# 01-UART.net
KiCad netlist of a schematic drawn in Altium Designer
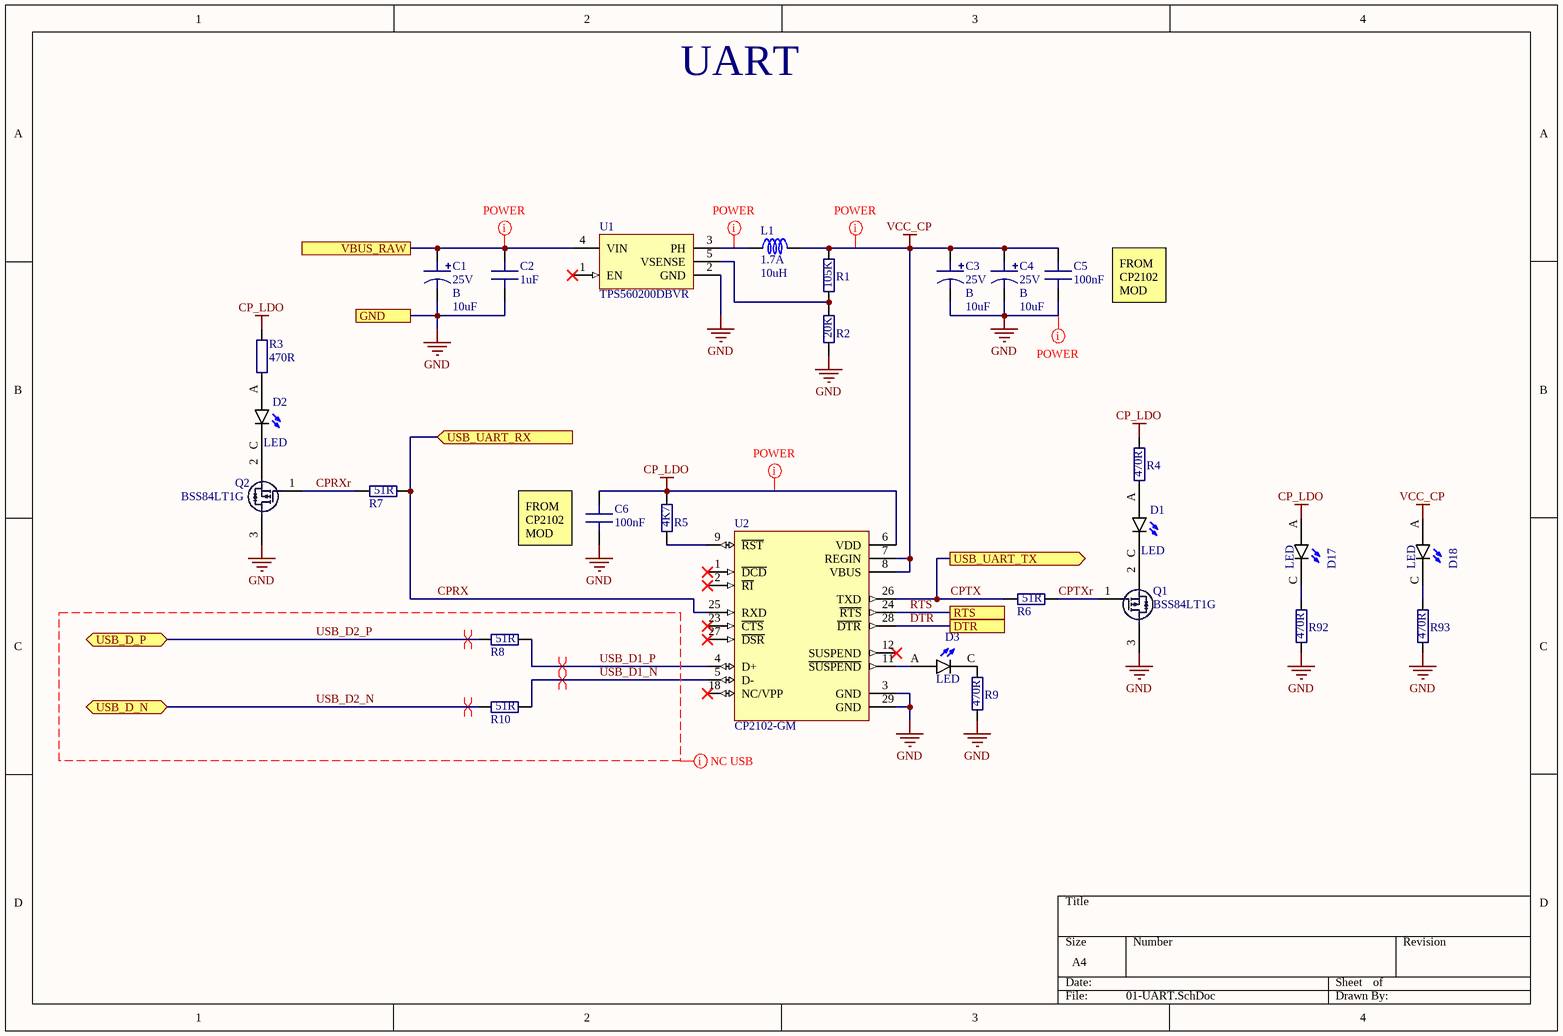
[diagram p0: 01-UART.SchDoc]

(export (version "E")
  (design (tool "Eeschema 10.0.6"))
  (components
    (comp (ref "C1")
      (value "10uF")
      (footprint "CAP_SIZE_B")
      (description "Tantalum capacitor")
      (fields (field (name "VOLTAGE") "25V") (field (name "SIZE") "B"))
      (libsource (lib "A.Shelestov_Capacitors") (part "CAP_B_10uF_25V"))
    )
    (comp (ref "C2")
      (value "1uF")
      (footprint "C0805")
      (description "Ceramic capacitor")
      (fields (field (name "VOLTAGE") "25V"))
      (libsource (lib "A.Shelestov_Capacitors") (part "C0805_1uF_25V"))
    )
    (comp (ref "C3")
      (value "10uF")
      (footprint "CAP_SIZE_B")
      (description "Tantalum capacitor")
      (fields (field (name "VOLTAGE") "25V") (field (name "SIZE") "B"))
      (libsource (lib "A.Shelestov_Capacitors") (part "CAP_B_10uF_25V"))
    )
    (comp (ref "C4")
      (value "10uF")
      (footprint "CAP_SIZE_B")
      (description "Tantalum capacitor")
      (fields (field (name "VOLTAGE") "25V") (field (name "SIZE") "B"))
      (libsource (lib "A.Shelestov_Capacitors") (part "CAP_B_10uF_25V"))
    )
    (comp (ref "C5")
      (value "100nF")
      (footprint "C0603")
      (description "Ceramic capacitor")
      (fields (field (name "VOLTAGE") "16V"))
      (libsource (lib "A.Shelestov_Capacitors") (part "C0603_100nF_16V"))
    )
    (comp (ref "C6")
      (value "100nF")
      (footprint "C0603")
      (description "Ceramic capacitor")
      (fields (field (name "VOLTAGE") "16V"))
      (libsource (lib "A.Shelestov_Capacitors") (part "C0603_100nF_16V"))
    )
    (comp (ref "D1")
      (value "LED")
      (footprint "LED_0604")
      (description "Led General")
      (fields (field (name "MF") "Dialight") (field (name "MP") "598-8140-107F"))
      (libsource (lib "ComponentsLib") (part "LED"))
    )
    (comp (ref "D2")
      (value "LED")
      (footprint "LED_0604")
      (description "Led General")
      (fields (field (name "MF") "Dialight") (field (name "MP") "598-8140-107F"))
      (libsource (lib "ComponentsLib") (part "LED"))
    )
    (comp (ref "D3")
      (value "LED")
      (footprint "LED_0604")
      (description "Led General")
      (fields (field (name "MF") "Dialight") (field (name "MP") "598-8140-107F"))
      (libsource (lib "ComponentsLib") (part "LED"))
    )
    (comp (ref "D17")
      (value "LED")
      (footprint "LED_0604")
      (description "Led General")
      (fields (field (name "MF") "Dialight") (field (name "MP") "598-8140-107F"))
      (libsource (lib "ComponentsLib") (part "LED"))
    )
    (comp (ref "D18")
      (value "LED")
      (footprint "LED_0604")
      (description "Led General")
      (fields (field (name "MF") "Dialight") (field (name "MP") "598-8140-107F"))
      (libsource (lib "ComponentsLib") (part "LED"))
    )
    (comp (ref "L1")
      (value "*")
      (footprint "L_CDRH6D28")
      (description "Inductor Generic")
      (fields (field (name "CURRENT") "1.7A") (field (name "INDUCTIVITY") "10uH"))
      (libsource (lib "A.Shelestov_Inductors") (part "L_CDRH6D28_10uH_1.7A"))
    )
    (comp (ref "Q1")
      (value "BSS84LT1G")
      (footprint "SOT-23_TO-236")
      (description "Power MOSFET Single P-Channel SOT-23 -50 V, 10 ")
      (libsource (lib "ComponentsLib") (part "BSS84LT1G"))
    )
    (comp (ref "Q2")
      (value "BSS84LT1G")
      (footprint "SOT-23_TO-236")
      (description "Power MOSFET Single P-Channel SOT-23 -50 V, 10 ")
      (libsource (lib "ComponentsLib") (part "BSS84LT1G"))
    )
    (comp (ref "R1")
      (value "~")
      (footprint "R0603")
      (description "Resistor General")
      (fields (field (name "TOLERANCE") "1%") (field (name "RESISTANCE") "105K"))
      (libsource (lib "A.Shelestov_Resistors") (part "R0603_105K_1%"))
    )
    (comp (ref "R2")
      (value "~")
      (footprint "R0603")
      (description "Resistor General")
      (fields (field (name "TOLERANCE") "1%") (field (name "RESISTANCE") "20K"))
      (libsource (lib "A.Shelestov_Resistors") (part "R0603_20K_1%"))
    )
    (comp (ref "R3")
      (value "~")
      (footprint "R0603")
      (description "Resistor General")
      (fields (field (name "TOLERANCE") "5%") (field (name "RESISTANCE") "470R"))
      (libsource (lib "A.Shelestov_Resistors") (part "R0603_470R"))
    )
    (comp (ref "R4")
      (value "~")
      (footprint "R0603")
      (description "Resistor General")
      (fields (field (name "TOLERANCE") "5%") (field (name "RESISTANCE") "470R"))
      (libsource (lib "A.Shelestov_Resistors") (part "R0603_470R"))
    )
    (comp (ref "R5")
      (value "~")
      (footprint "R0603")
      (description "Resistor General")
      (fields (field (name "TOLERANCE") "5%") (field (name "RESISTANCE") "4K7"))
      (libsource (lib "A.Shelestov_Resistors") (part "R0603_4K7"))
    )
    (comp (ref "R6")
      (value "~")
      (footprint "R0402")
      (description "Resistor General")
      (fields (field (name "RESISTANCE") "51R"))
      (libsource (lib "A.Shelestov_Resistors") (part "R0402_51R"))
    )
    (comp (ref "R7")
      (value "~")
      (footprint "R0402")
      (description "Resistor General")
      (fields (field (name "RESISTANCE") "51R"))
      (libsource (lib "A.Shelestov_Resistors") (part "R0402_51R"))
    )
    (comp (ref "R8")
      (value "~")
      (footprint "R0402")
      (description "Resistor General")
      (fields (field (name "RESISTANCE") "51R"))
      (libsource (lib "A.Shelestov_Resistors") (part "R0402_51R"))
    )
    (comp (ref "R9")
      (value "~")
      (footprint "R0603")
      (description "Resistor General")
      (fields (field (name "TOLERANCE") "5%") (field (name "RESISTANCE") "470R"))
      (libsource (lib "A.Shelestov_Resistors") (part "R0603_470R"))
    )
    (comp (ref "R10")
      (value "~")
      (footprint "R0402")
      (description "Resistor General")
      (fields (field (name "RESISTANCE") "51R"))
      (libsource (lib "A.Shelestov_Resistors") (part "R0402_51R"))
    )
    (comp (ref "R92")
      (value "~")
      (footprint "R0603")
      (description "Resistor General")
      (fields (field (name "TOLERANCE") "5%") (field (name "RESISTANCE") "470R"))
      (libsource (lib "A.Shelestov_Resistors") (part "R0603_470R"))
    )
    (comp (ref "R93")
      (value "~")
      (footprint "R0603")
      (description "Resistor General")
      (fields (field (name "TOLERANCE") "5%") (field (name "RESISTANCE") "470R"))
      (libsource (lib "A.Shelestov_Resistors") (part "R0603_470R"))
    )
    (comp (ref "U1")
      (value "TPS560200DBVR")
      (footprint "SOT-23-5")
      (description "TPS560200 4.5-V to 17-V Input, 500-mA Synchronous Step-Down Converter With Advanced Eco-Mode™")
      (libsource (lib "ComponentsLib") (part "TPS560200DBVR"))
    )
    (comp (ref "U2")
      (value "CP2102-GM")
      (footprint "QFN50P500X500X100-29N")
      (description "SINGLE-CHIP USB-TO-UART BRIDGE")
      (fields (field (name "MP") "CP2102GM") (field (name "MF") "Silicon Labs"))
      (libsource (lib "ComponentsLib") (part "CP2102-GM"))
    )
  )
  (nets
    (net (code "1") (name "/CPRX") (class "Default")
      (node (ref "R7") (pin "2") (pinfunction "2_2") (pintype "passive"))
      (node (ref "U2") (pin "25") (pinfunction "RXD_25") (pintype "input"))
    )
    (net (code "2") (name "/CPRXr") (class "Default")
      (node (ref "Q2") (pin "1") (pinfunction "G_1") (pintype "passive"))
      (node (ref "R7") (pin "1") (pinfunction "1_1") (pintype "passive"))
    )
    (net (code "3") (name "/CPTX") (class "Default")
      (node (ref "R6") (pin "1") (pinfunction "1_1") (pintype "passive"))
      (node (ref "U2") (pin "26") (pinfunction "TXD_26") (pintype "output"))
    )
    (net (code "4") (name "/CPTXr") (class "Default")
      (node (ref "Q1") (pin "1") (pinfunction "G_1") (pintype "passive"))
      (node (ref "R6") (pin "2") (pinfunction "2_2") (pintype "passive"))
    )
    (net (code "5") (name "/DTR") (class "Default")
      (node (ref "U2") (pin "28") (pinfunction "~{DTR}_28") (pintype "output"))
    )
    (net (code "6") (name "/RTS") (class "Default")
      (node (ref "U2") (pin "24") (pinfunction "~{RTS}_24") (pintype "output"))
    )
    (net (code "7") (name "/USB_D1_N") (class "Default")
      (node (ref "R10") (pin "2") (pinfunction "2_2") (pintype "passive"))
      (node (ref "U2") (pin "5") (pinfunction "D-_5") (pintype "bidirectional"))
    )
    (net (code "8") (name "/USB_D1_P") (class "Default")
      (node (ref "R8") (pin "2") (pinfunction "2_2") (pintype "passive"))
      (node (ref "U2") (pin "4") (pinfunction "D+_4") (pintype "bidirectional"))
    )
    (net (code "9") (name "/USB_D2_N") (class "Default")
      (node (ref "R10") (pin "1") (pinfunction "1_1") (pintype "passive"))
    )
    (net (code "10") (name "/USB_D2_P") (class "Default")
      (node (ref "R8") (pin "1") (pinfunction "1_1") (pintype "passive"))
    )
    (net (code "11") (name "/VBUS_RAW") (class "Default")
      (node (ref "C1") (pin "1") (pinfunction "1_1") (pintype "passive"))
      (node (ref "C2") (pin "2") (pinfunction "2_2") (pintype "passive"))
      (node (ref "U1") (pin "4") (pinfunction "VIN_4") (pintype "power_in"))
    )
    (net (code "12") (name "CP_LDO") (class "Default")
      (node (ref "C6") (pin "2") (pinfunction "2_2") (pintype "passive"))
      (node (ref "D17") (pin "A") (pinfunction "A_A") (pintype "passive"))
      (node (ref "R3") (pin "2") (pinfunction "2_2") (pintype "passive"))
      (node (ref "R4") (pin "2") (pinfunction "2_2") (pintype "passive"))
      (node (ref "R5") (pin "2") (pinfunction "2_2") (pintype "passive"))
      (node (ref "U2") (pin "6") (pinfunction "VDD_6") (pintype "power_in"))
    )
    (net (code "13") (name "GND") (class "Default")
      (node (ref "C1") (pin "2") (pinfunction "2_2") (pintype "passive"))
      (node (ref "C2") (pin "1") (pinfunction "1_1") (pintype "passive"))
      (node (ref "C3") (pin "2") (pinfunction "2_2") (pintype "passive"))
      (node (ref "C4") (pin "2") (pinfunction "2_2") (pintype "passive"))
      (node (ref "C5") (pin "1") (pinfunction "1_1") (pintype "passive"))
      (node (ref "C6") (pin "1") (pinfunction "1_1") (pintype "passive"))
      (node (ref "Q1") (pin "3") (pinfunction "D_3") (pintype "passive"))
      (node (ref "Q2") (pin "3") (pinfunction "D_3") (pintype "passive"))
      (node (ref "R2") (pin "1") (pinfunction "1_1") (pintype "passive"))
      (node (ref "R9") (pin "1") (pinfunction "1_1") (pintype "passive"))
      (node (ref "R92") (pin "1") (pinfunction "1_1") (pintype "passive"))
      (node (ref "R93") (pin "1") (pinfunction "1_1") (pintype "passive"))
      (node (ref "U1") (pin "2") (pinfunction "GND_2") (pintype "power_in"))
      (node (ref "U2") (pin "29") (pinfunction "GND_29") (pintype "power_in"))
      (node (ref "U2") (pin "3") (pinfunction "GND_3") (pintype "power_in"))
    )
    (net (code "14") (name "Net-(D1-PadA)") (class "Default")
      (node (ref "D1") (pin "A") (pinfunction "A_A") (pintype "passive"))
      (node (ref "R4") (pin "1") (pinfunction "1_1") (pintype "passive"))
    )
    (net (code "15") (name "Net-(D2-PadA)") (class "Default")
      (node (ref "D2") (pin "A") (pinfunction "A_A") (pintype "passive"))
      (node (ref "R3") (pin "1") (pinfunction "1_1") (pintype "passive"))
    )
    (net (code "16") (name "Net-(D3-PadC)") (class "Default")
      (node (ref "D3") (pin "C") (pinfunction "C_C") (pintype "passive"))
      (node (ref "R9") (pin "2") (pinfunction "2_2") (pintype "passive"))
    )
    (net (code "17") (name "Net-(D17-PadC)") (class "Default")
      (node (ref "D17") (pin "C") (pinfunction "C_C") (pintype "passive"))
      (node (ref "R92") (pin "2") (pinfunction "2_2") (pintype "passive"))
    )
    (net (code "18") (name "Net-(D18-PadC)") (class "Default")
      (node (ref "D18") (pin "C") (pinfunction "C_C") (pintype "passive"))
      (node (ref "R93") (pin "2") (pinfunction "2_2") (pintype "passive"))
    )
    (net (code "19") (name "Net-(Q1-S)") (class "Default")
      (node (ref "D1") (pin "C") (pinfunction "C_C") (pintype "passive"))
      (node (ref "Q1") (pin "2") (pinfunction "S_2") (pintype "passive"))
    )
    (net (code "20") (name "Net-(Q2-S)") (class "Default")
      (node (ref "D2") (pin "C") (pinfunction "C_C") (pintype "passive"))
      (node (ref "Q2") (pin "2") (pinfunction "S_2") (pintype "passive"))
    )
    (net (code "21") (name "Net-(U1-PH)") (class "Default")
      (node (ref "L1") (pin "1") (pinfunction "1_1") (pintype "passive"))
      (node (ref "U1") (pin "3") (pinfunction "PH_3") (pintype "power_in"))
    )
    (net (code "22") (name "Net-(U1-VSENSE)") (class "Default")
      (node (ref "R1") (pin "1") (pinfunction "1_1") (pintype "passive"))
      (node (ref "R2") (pin "2") (pinfunction "2_2") (pintype "passive"))
      (node (ref "U1") (pin "5") (pinfunction "VSENSE_5") (pintype "power_in"))
    )
    (net (code "23") (name "Net-(U2-~{RST})") (class "Default")
      (node (ref "R5") (pin "1") (pinfunction "1_1") (pintype "passive"))
      (node (ref "U2") (pin "9") (pinfunction "~{RST}_9") (pintype "bidirectional"))
    )
    (net (code "24") (name "Net-(U2-~{SUSPEND})") (class "Default")
      (node (ref "D3") (pin "A") (pinfunction "A_A") (pintype "passive"))
      (node (ref "U2") (pin "11") (pinfunction "~{SUSPEND}_11") (pintype "output"))
    )
    (net (code "25") (name "VCC_CP") (class "Default")
      (node (ref "C3") (pin "1") (pinfunction "1_1") (pintype "passive"))
      (node (ref "C4") (pin "1") (pinfunction "1_1") (pintype "passive"))
      (node (ref "C5") (pin "2") (pinfunction "2_2") (pintype "passive"))
      (node (ref "D18") (pin "A") (pinfunction "A_A") (pintype "passive"))
      (node (ref "L1") (pin "2") (pinfunction "2_2") (pintype "passive"))
      (node (ref "R1") (pin "2") (pinfunction "2_2") (pintype "passive"))
      (node (ref "U2") (pin "7") (pinfunction "REGIN_7") (pintype "power_in"))
      (node (ref "U2") (pin "8") (pinfunction "VBUS_8") (pintype "power_in"))
    )
    (net (code "26") (name "unconnected-(U1-EN-Pad1)") (class "Default")
      (node (ref "U1") (pin "1") (pinfunction "EN_1") (pintype "input+no_connect"))
    )
    (net (code "27") (name "unconnected-(U2-NC{slash}VPP-Pad18)") (class "Default")
      (node (ref "U2") (pin "18") (pinfunction "NC/VPP_18") (pintype "bidirectional+no_connect"))
    )
    (net (code "28") (name "unconnected-(U2-SUSPEND-Pad12)") (class "Default")
      (node (ref "U2") (pin "12") (pinfunction "SUSPEND_12") (pintype "output+no_connect"))
    )
    (net (code "29") (name "unconnected-(U2-~{CTS}-Pad23)") (class "Default")
      (node (ref "U2") (pin "23") (pinfunction "~{CTS}_23") (pintype "input+no_connect"))
    )
    (net (code "30") (name "unconnected-(U2-~{DCD}-Pad1)") (class "Default")
      (node (ref "U2") (pin "1") (pinfunction "~{DCD}_1") (pintype "input+no_connect"))
    )
    (net (code "31") (name "unconnected-(U2-~{DSR}-Pad27)") (class "Default")
      (node (ref "U2") (pin "27") (pinfunction "~{DSR}_27") (pintype "input+no_connect"))
    )
    (net (code "32") (name "unconnected-(U2-~{RI}-Pad2)") (class "Default")
      (node (ref "U2") (pin "2") (pinfunction "~{RI}_2") (pintype "input+no_connect"))
    )
  )
)
